# DAC_TLV5637.net
KiCad netlist of a schematic drawn in Altium Designer
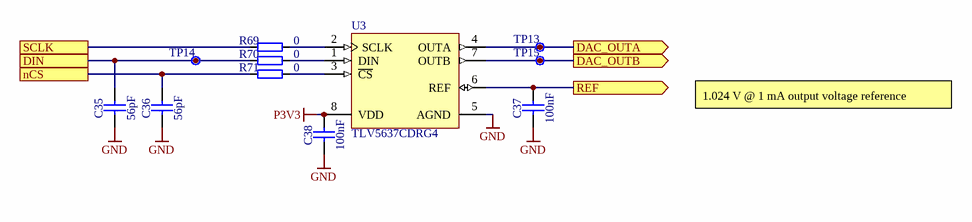
[diagram p0: DAC_TLV5637.SchDoc]

(export (version "E")
  (design (tool "Eeschema 10.0.6"))
  (components
    (comp (ref "C35")
      (value "56pF")
      (footprint "CAPC1005X55N")
      (description "Non-polarised capacitor")
      (fields
        (field (name "PART NUMBER") "CC0402_56PF_50V_5%_C0G")
        (field (name "VOLTAGE") "50V")
        (field (name "AUTHOR") "CERN DEM JLC")
      )
      (libsource (lib "Capacitors") (part "Capacitor - non polarized"))
    )
    (comp (ref "C36")
      (value "56pF")
      (footprint "CAPC1005X55N")
      (description "Non-polarised capacitor")
      (fields
        (field (name "PART NUMBER") "CC0402_56PF_50V_5%_C0G")
        (field (name "VOLTAGE") "50V")
        (field (name "AUTHOR") "CERN DEM JLC")
      )
      (libsource (lib "Capacitors") (part "Capacitor - non polarized"))
    )
    (comp (ref "C37")
      (value "100nF")
      (footprint "CAPC1005X55N")
      (description "Non-polarised capacitor")
      (fields
        (field (name "PART NUMBER") "CC0402_100NF_16V_10%_X5R")
        (field (name "VOLTAGE") "16V")
        (field (name "AUTHOR") "CERN DEM JLC")
      )
      (libsource (lib "Capacitors") (part "Capacitor - non polarized"))
    )
    (comp (ref "C38")
      (value "100nF")
      (footprint "CAPC1005X55N")
      (description "Non-polarised capacitor")
      (fields
        (field (name "PART NUMBER") "CC0402_100NF_16V_10%_X5R")
        (field (name "VOLTAGE") "16V")
        (field (name "AUTHOR") "CERN DEM JLC")
      )
      (libsource (lib "Capacitors") (part "Capacitor - non polarized"))
    )
    (comp (ref "R69")
      (value "0")
      (footprint "RESC1005X40N")
      (description "Resistor")
      (fields
        (field (name "PART NUMBER") "R0402_0R_JUMPER")
        (field (name "MANUFACTURER") "GENERIC")
        (field (name "AUTHOR") "CERN DEM JLC")
      )
      (libsource (lib "Resistors") (part "Resistor"))
    )
    (comp (ref "R70")
      (value "0")
      (footprint "RESC1005X40N")
      (description "Resistor")
      (fields
        (field (name "PART NUMBER") "R0402_0R_JUMPER")
        (field (name "MANUFACTURER") "GENERIC")
        (field (name "AUTHOR") "CERN DEM JLC")
      )
      (libsource (lib "Resistors") (part "Resistor"))
    )
    (comp (ref "R71")
      (value "0")
      (footprint "RESC1005X40N")
      (description "Resistor")
      (fields
        (field (name "PART NUMBER") "R0402_0R_JUMPER")
        (field (name "MANUFACTURER") "GENERIC")
        (field (name "AUTHOR") "CERN DEM JLC")
      )
      (libsource (lib "Resistors") (part "Resistor"))
    )
    (comp (ref "TP13")
      (value "Plated Hole")
      (footprint "c130h60")
      (description "Single Terminal Socket")
      (fields (field (name "PART NUMBER") "PLATED_HOLE0.6_PAD1.3") (field (name "AUTHOR") "CERN DEM MR"))
      (libsource (lib "Eletro-mechanical") (part "Single Terminal Socket"))
    )
    (comp (ref "TP14")
      (value "Plated Hole")
      (footprint "c130h60")
      (description "Single Terminal Socket")
      (fields (field (name "PART NUMBER") "PLATED_HOLE0.6_PAD1.3") (field (name "AUTHOR") "CERN DEM MR"))
      (libsource (lib "Eletro-mechanical") (part "Single Terminal Socket"))
    )
    (comp (ref "TP15")
      (value "Plated Hole")
      (footprint "c130h60")
      (description "Single Terminal Socket")
      (fields (field (name "PART NUMBER") "PLATED_HOLE0.6_PAD1.3") (field (name "AUTHOR") "CERN DEM MR"))
      (libsource (lib "Eletro-mechanical") (part "Single Terminal Socket"))
    )
    (comp (ref "U3")
      (value "TLV5637CDRG4")
      (footprint "TI-D8_N")
      (fields (field (name "MANUFACTURER") "Texas Instruments"))
      (libsource (lib "Altium Content Vault") (part "TI-TLV5625_26_37_38-D8"))
    )
  )
  (nets
    (net (code "1") (name "/DAC_OUTA") (class "Default")
      (node (ref "TP13") (pin "1") (pinfunction "1_1") (pintype "bidirectional"))
      (node (ref "U3") (pin "4") (pinfunction "OUTA_4") (pintype "output"))
    )
    (net (code "2") (name "/DAC_OUTB") (class "Default")
      (node (ref "TP15") (pin "1") (pinfunction "1_1") (pintype "bidirectional"))
      (node (ref "U3") (pin "7") (pinfunction "OUTB_7") (pintype "output"))
    )
    (net (code "3") (name "/DIN") (class "Default")
      (node (ref "C35") (pin "2") (pinfunction "2_2") (pintype "passive"))
      (node (ref "R70") (pin "1") (pinfunction "1_1") (pintype "passive"))
      (node (ref "TP14") (pin "1") (pinfunction "1_1") (pintype "bidirectional"))
    )
    (net (code "4") (name "/REF") (class "Default")
      (node (ref "C37") (pin "2") (pinfunction "2_2") (pintype "passive"))
      (node (ref "U3") (pin "6") (pinfunction "REF_6") (pintype "bidirectional"))
    )
    (net (code "5") (name "/SCLK") (class "Default")
      (node (ref "R69") (pin "1") (pinfunction "1_1") (pintype "passive"))
    )
    (net (code "6") (name "/nCS") (class "Default")
      (node (ref "C36") (pin "2") (pinfunction "2_2") (pintype "passive"))
      (node (ref "R71") (pin "1") (pinfunction "1_1") (pintype "passive"))
    )
    (net (code "7") (name "GND") (class "Default")
      (node (ref "C35") (pin "1") (pinfunction "1_1") (pintype "passive"))
      (node (ref "C36") (pin "1") (pinfunction "1_1") (pintype "passive"))
      (node (ref "C37") (pin "1") (pinfunction "1_1") (pintype "passive"))
      (node (ref "C38") (pin "1") (pinfunction "1_1") (pintype "passive"))
      (node (ref "U3") (pin "5") (pinfunction "AGND_5") (pintype "power_in"))
    )
    (net (code "8") (name "Net-(U3-DIN)") (class "Default")
      (node (ref "R70") (pin "2") (pinfunction "2_2") (pintype "passive"))
      (node (ref "U3") (pin "1") (pinfunction "DIN_1") (pintype "input"))
    )
    (net (code "9") (name "Net-(U3-SCLK)") (class "Default")
      (node (ref "R69") (pin "2") (pinfunction "2_2") (pintype "passive"))
      (node (ref "U3") (pin "2") (pinfunction "SCLK_2") (pintype "input"))
    )
    (net (code "10") (name "Net-(U3-~{CS})") (class "Default")
      (node (ref "R71") (pin "2") (pinfunction "2_2") (pintype "passive"))
      (node (ref "U3") (pin "3") (pinfunction "~{CS}_3") (pintype "input"))
    )
    (net (code "11") (name "P3V3") (class "Default")
      (node (ref "C38") (pin "2") (pinfunction "2_2") (pintype "passive"))
      (node (ref "U3") (pin "8") (pinfunction "VDD_8") (pintype "power_in"))
    )
  )
)
